# usb2serial_ft232rl.net
KiCad netlist of a schematic drawn in Altium Designer
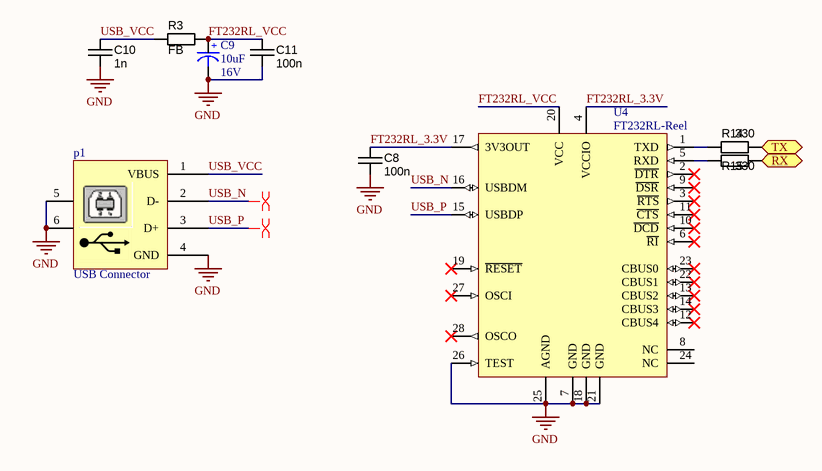
[diagram p0: usb2serial_ft232rl.SchDoc]

(export (version "E")
  (design (tool "Eeschema 10.0.6"))
  (components
    (comp (ref "C8")
      (value "100n")
      (footprint "CAPC1608X90N")
      (description "Capacitor 0603")
      (fields (field (name "TOLERANCE") "±10%"))
      (libsource (lib "PBL - Capacitors") (part "CAPC_1n_0603_X7R_100V_10%"))
    )
    (comp (ref "C9")
      (value "10uF")
      (footprint "WCAP-PSLP_4x5.5")
      (description "Polar Capacitor")
      (fields (field (name "VOLTAGE") "16V") (field (name "DESIGNER") "Saeid Jorablo"))
      (libsource (lib "My Library") (part "Cap-Polar"))
    )
    (comp (ref "C10")
      (value "1n")
      (footprint "CAPC1608X90N")
      (description "Capacitor 0603")
      (fields (field (name "TOLERANCE") "±10%"))
      (libsource (lib "PBL - Capacitors") (part "CAPC_1n_0603_X7R_100V_10%"))
    )
    (comp (ref "C11")
      (value "100n")
      (footprint "CAPC1608X90N")
      (description "Capacitor 0603")
      (fields (field (name "TOLERANCE") "±10%"))
      (libsource (lib "PBL - Capacitors") (part "CAPC_1n_0603_X7R_100V_10%"))
    )
    (comp (ref "p1")
      (value "USB Connector")
      (footprint "USB2.5-2H4E")
      (description "USB Connector-B Type")
      (fields (field (name "DESIGNER") "Eng. Saeid Jorablo"))
      (libsource (lib "My Library") (part "USB"))
    )
    (comp (ref "R3")
      (value "FB")
      (footprint "RESC1608X55N")
      (description "Resistor 0603")
      (fields (field (name "TOLERANCE") "±5%"))
      (libsource (lib "PBL - Resistors") (part "RES_2K2_0603_5%"))
    )
    (comp (ref "R14")
      (value "330")
      (footprint "RESC1608X55N")
      (description "Resistor 0603")
      (fields (field (name "TOLERANCE") "±5%"))
      (libsource (lib "PBL - Resistors") (part "RES_2K2_0603_5%"))
    )
    (comp (ref "R15")
      (value "330")
      (footprint "RESC1608X55N")
      (description "Resistor 0603")
      (fields (field (name "TOLERANCE") "±5%"))
      (libsource (lib "PBL - Resistors") (part "RES_2K2_0603_5%"))
    )
    (comp (ref "U4")
      (value "FT232RL-Reel")
      (footprint "SSOP-28_M")
      (description "USB UART Asynchronous Serial Data Transfer Chip, 28-pin SSOP, Tape and Reel")
      (fields (field (name "MANUFACTURER") "FTDI"))
      (libsource (lib "FTDI FT Series") (part "FT232RL-Reel"))
    )
  )
  (nets
    (net (code "1") (name "/FT232RL_3.3V") (class "Default")
      (node (ref "C8") (pin "1") (pintype "passive"))
      (node (ref "U4") (pin "17") (pinfunction "3V3OUT_17") (pintype "output"))
      (node (ref "U4") (pin "4") (pinfunction "VCCIO_4") (pintype "power_in"))
    )
    (net (code "2") (name "/FT232RL_VCC") (class "Default")
      (node (ref "C11") (pin "2") (pintype "passive"))
      (node (ref "C9") (pin "1") (pinfunction "+_1") (pintype "passive"))
      (node (ref "R3") (pin "2") (pinfunction "2_2") (pintype "passive"))
      (node (ref "U4") (pin "20") (pinfunction "VCC_20") (pintype "power_in"))
    )
    (net (code "3") (name "/RX") (class "Default")
      (node (ref "R15") (pin "2") (pinfunction "2_2") (pintype "passive"))
    )
    (net (code "4") (name "/TX") (class "Default")
      (node (ref "R14") (pin "2") (pinfunction "2_2") (pintype "passive"))
    )
    (net (code "5") (name "/USB_N") (class "Default")
      (node (ref "U4") (pin "16") (pinfunction "USBDM_16") (pintype "bidirectional"))
      (node (ref "p1") (pin "2") (pinfunction "D-_2") (pintype "passive"))
    )
    (net (code "6") (name "/USB_P") (class "Default")
      (node (ref "U4") (pin "15") (pinfunction "USBDP_15") (pintype "bidirectional"))
      (node (ref "p1") (pin "3") (pinfunction "D+_3") (pintype "passive"))
    )
    (net (code "7") (name "/USB_VCC") (class "Default")
      (node (ref "C10") (pin "2") (pintype "passive"))
      (node (ref "R3") (pin "1") (pinfunction "1_1") (pintype "passive"))
      (node (ref "p1") (pin "1") (pinfunction "VBUS_1") (pintype "power_in"))
    )
    (net (code "8") (name "GND") (class "Default")
      (node (ref "C10") (pin "1") (pintype "passive"))
      (node (ref "C11") (pin "1") (pintype "passive"))
      (node (ref "C8") (pin "2") (pintype "passive"))
      (node (ref "C9") (pin "2") (pinfunction "-_2") (pintype "passive"))
      (node (ref "U4") (pin "18") (pinfunction "GND_18") (pintype "power_in"))
      (node (ref "U4") (pin "21") (pinfunction "GND_21") (pintype "power_in"))
      (node (ref "U4") (pin "25") (pinfunction "AGND_25") (pintype "power_in"))
      (node (ref "U4") (pin "26") (pinfunction "TEST_26") (pintype "input"))
      (node (ref "U4") (pin "7") (pinfunction "GND_7") (pintype "power_in"))
      (node (ref "p1") (pin "4") (pinfunction "GND_4") (pintype "power_in"))
      (node (ref "p1") (pin "5") (pinfunction "5_5") (pintype "passive"))
      (node (ref "p1") (pin "6") (pinfunction "6_6") (pintype "passive"))
    )
    (net (code "9") (name "Net-(U4-RXD)") (class "Default")
      (node (ref "R15") (pin "1") (pinfunction "1_1") (pintype "passive"))
      (node (ref "U4") (pin "5") (pinfunction "RXD_5") (pintype "input"))
    )
    (net (code "10") (name "Net-(U4-TXD)") (class "Default")
      (node (ref "R14") (pin "1") (pinfunction "1_1") (pintype "passive"))
      (node (ref "U4") (pin "1") (pinfunction "TXD_1") (pintype "output"))
    )
    (net (code "11") (name "unconnected-(U4-CBUS0-Pad23)") (class "Default")
      (node (ref "U4") (pin "23") (pinfunction "CBUS0_23") (pintype "bidirectional+no_connect"))
    )
    (net (code "12") (name "unconnected-(U4-CBUS1-Pad22)") (class "Default")
      (node (ref "U4") (pin "22") (pinfunction "CBUS1_22") (pintype "bidirectional+no_connect"))
    )
    (net (code "13") (name "unconnected-(U4-CBUS2-Pad13)") (class "Default")
      (node (ref "U4") (pin "13") (pinfunction "CBUS2_13") (pintype "bidirectional+no_connect"))
    )
    (net (code "14") (name "unconnected-(U4-CBUS3-Pad14)") (class "Default")
      (node (ref "U4") (pin "14") (pinfunction "CBUS3_14") (pintype "bidirectional+no_connect"))
    )
    (net (code "15") (name "unconnected-(U4-CBUS4-Pad12)") (class "Default")
      (node (ref "U4") (pin "12") (pinfunction "CBUS4_12") (pintype "bidirectional+no_connect"))
    )
    (net (code "16") (name "unconnected-(U4-NC-Pad8)") (class "Default")
      (node (ref "U4") (pin "8") (pinfunction "NC_8") (pintype "passive"))
    )
    (net (code "17") (name "unconnected-(U4-NC-Pad24)") (class "Default")
      (node (ref "U4") (pin "24") (pinfunction "NC_24") (pintype "passive"))
    )
    (net (code "18") (name "unconnected-(U4-OSCI-Pad27)") (class "Default")
      (node (ref "U4") (pin "27") (pinfunction "OSCI_27") (pintype "input+no_connect"))
    )
    (net (code "19") (name "unconnected-(U4-OSCO-Pad28)") (class "Default")
      (node (ref "U4") (pin "28") (pinfunction "OSCO_28") (pintype "output+no_connect"))
    )
    (net (code "20") (name "unconnected-(U4-~{CTS}-Pad11)") (class "Default")
      (node (ref "U4") (pin "11") (pinfunction "~{CTS}_11") (pintype "input+no_connect"))
    )
    (net (code "21") (name "unconnected-(U4-~{DCD}-Pad10)") (class "Default")
      (node (ref "U4") (pin "10") (pinfunction "~{DCD}_10") (pintype "input+no_connect"))
    )
    (net (code "22") (name "unconnected-(U4-~{DSR}-Pad9)") (class "Default")
      (node (ref "U4") (pin "9") (pinfunction "~{DSR}_9") (pintype "input+no_connect"))
    )
    (net (code "23") (name "unconnected-(U4-~{DTR}-Pad2)") (class "Default")
      (node (ref "U4") (pin "2") (pinfunction "~{DTR}_2") (pintype "output+no_connect"))
    )
    (net (code "24") (name "unconnected-(U4-~{RESET}-Pad19)") (class "Default")
      (node (ref "U4") (pin "19") (pinfunction "~{RESET}_19") (pintype "input+no_connect"))
    )
    (net (code "25") (name "unconnected-(U4-~{RI}-Pad6)") (class "Default")
      (node (ref "U4") (pin "6") (pinfunction "~{RI}_6") (pintype "input+no_connect"))
    )
    (net (code "26") (name "unconnected-(U4-~{RTS}-Pad3)") (class "Default")
      (node (ref "U4") (pin "3") (pinfunction "~{RTS}_3") (pintype "output+no_connect"))
    )
  )
)
